# HDMI_Connector_for_RK3399.net
KiCad netlist of a schematic drawn in Altium Designer
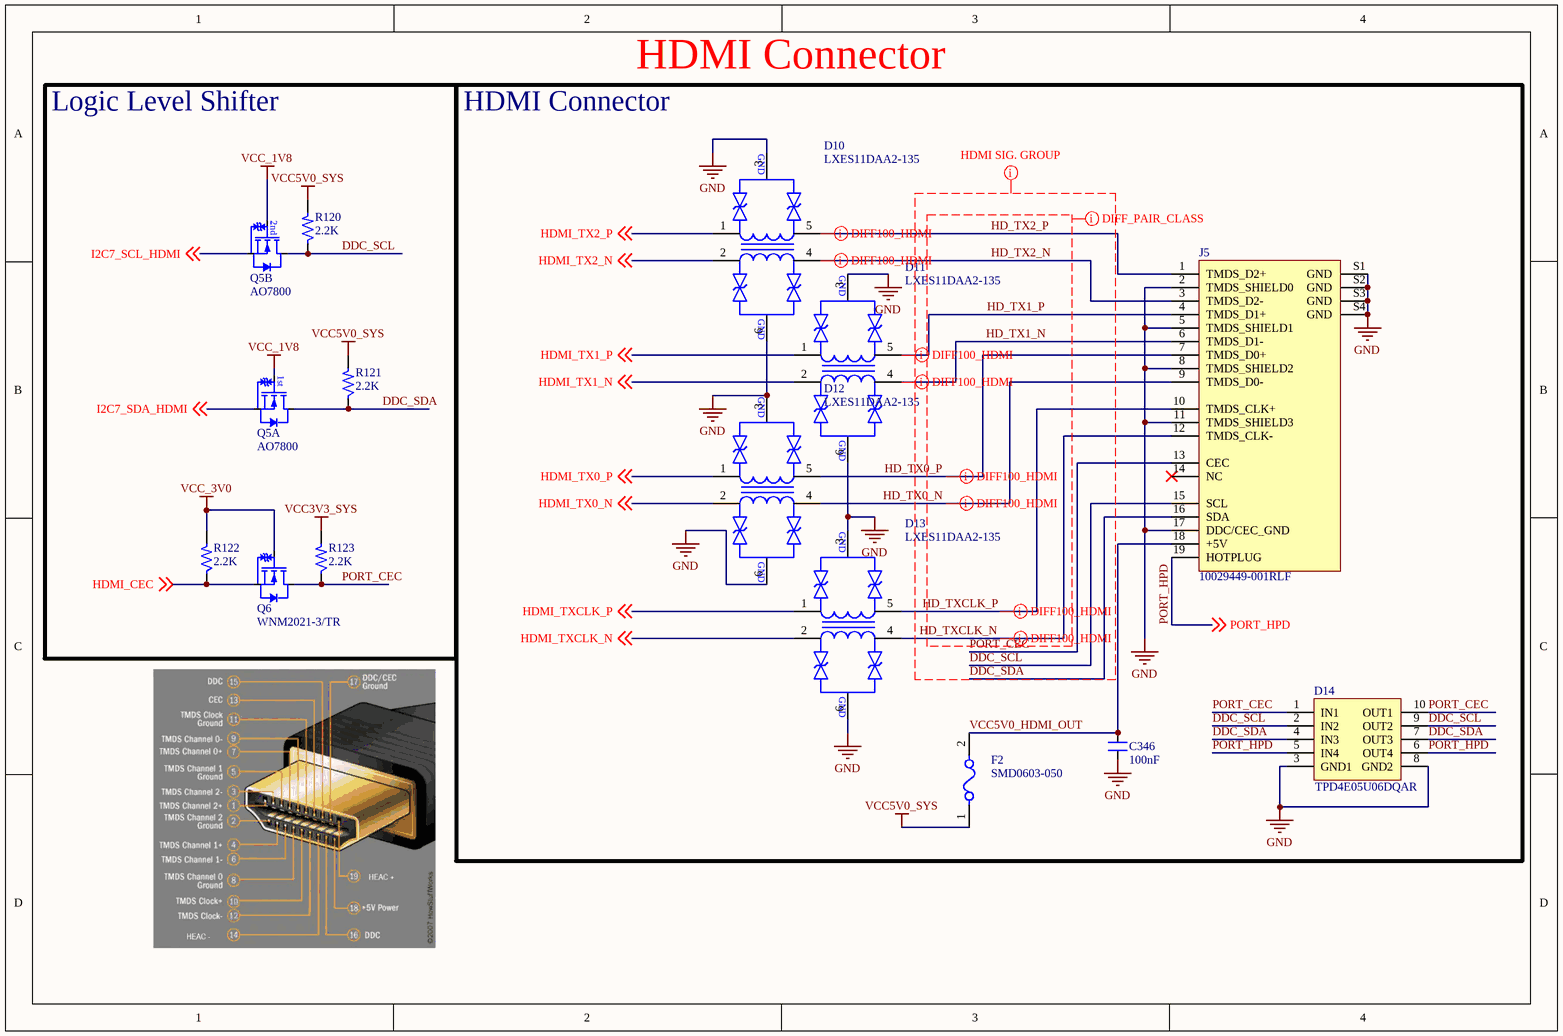
[diagram p0: HDMI Connector for RK3399.SchDoc]

(export (version "E")
  (design (tool "Eeschema 10.0.6"))
  (components
    (comp (ref "C346")
      (value "100nF")
      (footprint "CAP_0603")
      (description "0.1µF ±10% 10V Ceramic Capacitor X7R 0603 (1608 Metric)")
      (fields
        (field (name "MANUFACTURER") "Yageo")
        (field (name "MANUFACTURER PART NUMBER") "CC0603KRX7R6BB104")
      )
      (libsource (lib "RK3399 _Module_Schlib") (part "CAP_100nF-10V-5%-0603"))
    )
    (comp (ref "D10")
      (value "LXES11DAA2-135")
      (footprint "DIO_LXES11D_SMD")
      (description "Clamp Ipp Tvs Diode Surface Mount 10-SMD")
      (fields (field (name "MANUFACTURER") "Murata Electronics"))
      (libsource (lib "RK3399 _Module_Schlib") (part "DIO-T-A_5V-6SMD"))
    )
    (comp (ref "D11")
      (value "LXES11DAA2-135")
      (footprint "DIO_LXES11D_SMD")
      (description "Clamp Ipp Tvs Diode Surface Mount 10-SMD")
      (fields (field (name "MANUFACTURER") "Murata Electronics"))
      (libsource (lib "RK3399 _Module_Schlib") (part "DIO-T-A_5V-6SMD"))
    )
    (comp (ref "D12")
      (value "LXES11DAA2-135")
      (footprint "DIO_LXES11D_SMD")
      (description "Clamp Ipp Tvs Diode Surface Mount 10-SMD")
      (fields (field (name "MANUFACTURER") "Murata Electronics"))
      (libsource (lib "RK3399 _Module_Schlib") (part "DIO-T-A_5V-6SMD"))
    )
    (comp (ref "D13")
      (value "LXES11DAA2-135")
      (footprint "DIO_LXES11D_SMD")
      (description "Clamp Ipp Tvs Diode Surface Mount 10-SMD")
      (fields (field (name "MANUFACTURER") "Murata Electronics"))
      (libsource (lib "RK3399 _Module_Schlib") (part "DIO-T-A_5V-6SMD"))
    )
    (comp (ref "D14")
      (value "TPD4E05U06DQAR")
      (footprint "DIO_USON-10_SMD")
      (description "14V Clamp 2.5A (8/20µs) Ipp Tvs Diode Surface Mount 10-USON (2.5x1)")
      (fields (field (name "MANUFACTURER") "Texas Instruments"))
      (libsource (lib "RK3399 _Module_Schlib") (part "DIO-T_5.5V-14V-2.5A-10-USON"))
    )
    (comp (ref "F2")
      (value "SMD0603-050")
      (footprint "RES_0603")
      (description "6V 1A 0603 PTC Resettable Fuses RoHS")
      (fields (field (name "MANUFACTURER") "TECHFUSE"))
      (libsource (lib "RK3399 _Module_Schlib") (part "FUSE_1A-6V-0603"))
    )
    (comp (ref "J5")
      (value "10029449-001RLF")
      (footprint "CON19_19.6_10029449-001RLF_TH_RA")
      (description "HDMI HDMI 1.4 Receptacle Connector 19 Position Surface Mount, Right Angle; Through Hole")
      (fields (field (name "MANUFACTURER") "Amphenol ICC (FCI)"))
      (libsource (lib "EsteemPCB_COB_Course_intlib") (part "CON-HDMI_10029449-001RLF-RA-TH"))
    )
    (comp (ref "Q5")
      (value "AO7800")
      (footprint "SOT363-6")
      (description "DualNChannel 20V 900mA 900mV @ 250uA 300mΩ @ 900mA,4.5V 300mW SC-70-6(SOT-363) MOSFET RoHS")
      (fields (field (name "MANUFACTURER") "Alpha & Omega Semicon"))
      (libsource (lib "RK3399 _Module_Schlib") (part "MOSFET-N_20V-0.9A-SOT-363"))
    )
    (comp (ref "Q6")
      (value "WNM2021-3/TR")
      (footprint "SOT-323-3")
      (description "N Channel 20V 820mA 850mV @ 250uA 310mΩ @ 550mA,4.5V 310mW SOT-323(SC-70) MOSFET RoHS")
      (fields (field (name "MANUFACTURER") "WILLSEMI(Will Semicon)"))
      (libsource (lib "RK3399 _Module_Schlib") (part "MOSFET-N_20V-820mA-SOT-323"))
    )
    (comp (ref "R120")
      (value "2.2K")
      (footprint "RES_0603")
      (description "2.2 kOhms ±1% 0.1W, 1/10W Chip Resistor 0603 (1608 Metric) Thick Film")
      (fields
        (field (name "MANUFACTURER") "Yageo")
        (field (name "MANUFACTURER PART NUMBER") "RC0603FR-072K2L")
      )
      (libsource (lib "RK3399 _Module_Schlib") (part "RES_2.2K-0.1W-1%-0603"))
    )
    (comp (ref "R121")
      (value "2.2K")
      (footprint "RES_0603")
      (description "2.2 kOhms ±1% 0.1W, 1/10W Chip Resistor 0603 (1608 Metric) Thick Film")
      (fields
        (field (name "MANUFACTURER") "Yageo")
        (field (name "MANUFACTURER PART NUMBER") "RC0603FR-072K2L")
      )
      (libsource (lib "RK3399 _Module_Schlib") (part "RES_2.2K-0.1W-1%-0603"))
    )
    (comp (ref "R122")
      (value "2.2K")
      (footprint "RES_0603")
      (description "2.2 kOhms ±1% 0.1W, 1/10W Chip Resistor 0603 (1608 Metric) Thick Film")
      (fields
        (field (name "MANUFACTURER") "Yageo")
        (field (name "MANUFACTURER PART NUMBER") "RC0603FR-072K2L")
      )
      (libsource (lib "RK3399 _Module_Schlib") (part "RES_2.2K-0.1W-1%-0603"))
    )
    (comp (ref "R123")
      (value "2.2K")
      (footprint "RES_0603")
      (description "2.2 kOhms ±1% 0.1W, 1/10W Chip Resistor 0603 (1608 Metric) Thick Film")
      (fields
        (field (name "MANUFACTURER") "Yageo")
        (field (name "MANUFACTURER PART NUMBER") "RC0603FR-072K2L")
      )
      (libsource (lib "RK3399 _Module_Schlib") (part "RES_2.2K-0.1W-1%-0603"))
    )
  )
  (nets
    (net (code "1") (name "/DDC_SCL") (class "Default")
      (node (ref "D14") (pin "2") (pinfunction "IN2_2") (pintype "passive"))
      (node (ref "D14") (pin "9") (pinfunction "OUT2_9") (pintype "passive"))
      (node (ref "J5") (pin "15") (pinfunction "SCL_15") (pintype "passive"))
      (node (ref "Q5") (pin "3") (pinfunction "D2_3") (pintype "passive"))
      (node (ref "R120") (pin "1") (pinfunction "1_1") (pintype "passive"))
    )
    (net (code "2") (name "/DDC_SDA") (class "Default")
      (node (ref "D14") (pin "4") (pinfunction "IN3_4") (pintype "passive"))
      (node (ref "D14") (pin "7") (pinfunction "OUT3_7") (pintype "passive"))
      (node (ref "J5") (pin "16") (pinfunction "SDA_16") (pintype "passive"))
      (node (ref "Q5") (pin "6") (pinfunction "D1_6") (pintype "passive"))
      (node (ref "R121") (pin "1") (pinfunction "1_1") (pintype "passive"))
    )
    (net (code "3") (name "/HD_TX0_N") (class "Default")
      (node (ref "D12") (pin "4") (pinfunction "4_4") (pintype "passive"))
      (node (ref "J5") (pin "9") (pinfunction "TMDS_D0-_9") (pintype "passive"))
    )
    (net (code "4") (name "/HD_TX0_P") (class "Default")
      (node (ref "D12") (pin "5") (pinfunction "5_5") (pintype "passive"))
      (node (ref "J5") (pin "7") (pinfunction "TMDS_D0+_7") (pintype "passive"))
    )
    (net (code "5") (name "/HD_TX1_N") (class "Default")
      (node (ref "D11") (pin "4") (pinfunction "4_4") (pintype "passive"))
      (node (ref "J5") (pin "6") (pinfunction "TMDS_D1-_6") (pintype "passive"))
    )
    (net (code "6") (name "/HD_TX1_P") (class "Default")
      (node (ref "D11") (pin "5") (pinfunction "5_5") (pintype "passive"))
      (node (ref "J5") (pin "4") (pinfunction "TMDS_D1+_4") (pintype "passive"))
    )
    (net (code "7") (name "/HD_TX2_N") (class "Default")
      (node (ref "D10") (pin "4") (pinfunction "4_4") (pintype "passive"))
      (node (ref "J5") (pin "3") (pinfunction "TMDS_D2-_3") (pintype "passive"))
    )
    (net (code "8") (name "/HD_TX2_P") (class "Default")
      (node (ref "D10") (pin "5") (pinfunction "5_5") (pintype "passive"))
      (node (ref "J5") (pin "1") (pinfunction "TMDS_D2+_1") (pintype "passive"))
    )
    (net (code "9") (name "/HD_TXCLK_N") (class "Default")
      (node (ref "D13") (pin "4") (pinfunction "4_4") (pintype "passive"))
      (node (ref "J5") (pin "12") (pinfunction "TMDS_CLK-_12") (pintype "passive"))
    )
    (net (code "10") (name "/HD_TXCLK_P") (class "Default")
      (node (ref "D13") (pin "5") (pinfunction "5_5") (pintype "passive"))
      (node (ref "J5") (pin "10") (pinfunction "TMDS_CLK+_10") (pintype "passive"))
    )
    (net (code "11") (name "/PORT_CEC") (class "Default")
      (node (ref "D14") (pin "1") (pinfunction "IN1_1") (pintype "passive"))
      (node (ref "D14") (pin "10") (pinfunction "OUT1_10") (pintype "passive"))
      (node (ref "J5") (pin "13") (pinfunction "CEC_13") (pintype "passive"))
      (node (ref "Q6") (pin "3") (pinfunction "D_3") (pintype "passive"))
      (node (ref "R123") (pin "1") (pinfunction "1_1") (pintype "passive"))
    )
    (net (code "12") (name "/VCC5V0_HDMI_OUT") (class "Default")
      (node (ref "C346") (pin "2") (pinfunction "2_2") (pintype "passive"))
      (node (ref "F2") (pin "2") (pinfunction "2_2") (pintype "passive"))
      (node (ref "J5") (pin "18") (pinfunction "+5V_18") (pintype "passive"))
    )
    (net (code "13") (name "GND") (class "Default")
      (node (ref "C346") (pin "1") (pinfunction "1_1") (pintype "passive"))
      (node (ref "D10") (pin "3") (pinfunction "5_3") (pintype "passive"))
      (node (ref "D10") (pin "6") (pinfunction "6_6") (pintype "passive"))
      (node (ref "D11") (pin "3") (pinfunction "5_3") (pintype "passive"))
      (node (ref "D11") (pin "6") (pinfunction "6_6") (pintype "passive"))
      (node (ref "D12") (pin "3") (pinfunction "5_3") (pintype "passive"))
      (node (ref "D12") (pin "6") (pinfunction "6_6") (pintype "passive"))
      (node (ref "D13") (pin "3") (pinfunction "5_3") (pintype "passive"))
      (node (ref "D13") (pin "6") (pinfunction "6_6") (pintype "passive"))
      (node (ref "D14") (pin "3") (pinfunction "GND1_3") (pintype "passive"))
      (node (ref "D14") (pin "8") (pinfunction "GND2_8") (pintype "passive"))
      (node (ref "J5") (pin "11") (pinfunction "TMDS_SHIELD3_11") (pintype "passive"))
      (node (ref "J5") (pin "17") (pinfunction "DDC/CEC_GND_17") (pintype "passive"))
      (node (ref "J5") (pin "2") (pinfunction "TMDS_SHIELD0_2") (pintype "passive"))
      (node (ref "J5") (pin "5") (pinfunction "TMDS_SHIELD1_5") (pintype "passive"))
      (node (ref "J5") (pin "8") (pinfunction "TMDS_SHIELD2_8") (pintype "passive"))
      (node (ref "J5") (pin "S1") (pinfunction "GND_S1") (pintype "passive"))
      (node (ref "J5") (pin "S2") (pinfunction "GND_S2") (pintype "passive"))
      (node (ref "J5") (pin "S3") (pinfunction "GND_S3") (pintype "passive"))
      (node (ref "J5") (pin "S4") (pinfunction "GND_S4") (pintype "passive"))
    )
    (net (code "14") (name "HDMI_CEC") (class "Default")
      (node (ref "Q6") (pin "2") (pinfunction "S_2") (pintype "passive"))
      (node (ref "R122") (pin "1") (pinfunction "1_1") (pintype "passive"))
    )
    (net (code "15") (name "HDMI_TX0_N") (class "Default")
      (node (ref "D12") (pin "2") (pinfunction "2_2") (pintype "passive"))
    )
    (net (code "16") (name "HDMI_TX0_P") (class "Default")
      (node (ref "D12") (pin "1") (pinfunction "1_1") (pintype "passive"))
    )
    (net (code "17") (name "HDMI_TX1_N") (class "Default")
      (node (ref "D11") (pin "2") (pinfunction "2_2") (pintype "passive"))
    )
    (net (code "18") (name "HDMI_TX1_P") (class "Default")
      (node (ref "D11") (pin "1") (pinfunction "1_1") (pintype "passive"))
    )
    (net (code "19") (name "HDMI_TX2_N") (class "Default")
      (node (ref "D10") (pin "2") (pinfunction "2_2") (pintype "passive"))
    )
    (net (code "20") (name "HDMI_TX2_P") (class "Default")
      (node (ref "D10") (pin "1") (pinfunction "1_1") (pintype "passive"))
    )
    (net (code "21") (name "HDMI_TXCLK_N") (class "Default")
      (node (ref "D13") (pin "2") (pinfunction "2_2") (pintype "passive"))
    )
    (net (code "22") (name "HDMI_TXCLK_P") (class "Default")
      (node (ref "D13") (pin "1") (pinfunction "1_1") (pintype "passive"))
    )
    (net (code "23") (name "I2C7_SCL_HDMI") (class "Default")
      (node (ref "Q5") (pin "4") (pinfunction "S2_4") (pintype "passive"))
    )
    (net (code "24") (name "I2C7_SDA_HDMI") (class "Default")
      (node (ref "Q5") (pin "1") (pinfunction "S1_1") (pintype "passive"))
    )
    (net (code "25") (name "PORT_HPD") (class "Default")
      (node (ref "D14") (pin "5") (pinfunction "IN4_5") (pintype "passive"))
      (node (ref "D14") (pin "6") (pinfunction "OUT4_6") (pintype "passive"))
      (node (ref "J5") (pin "19") (pinfunction "HOTPLUG_19") (pintype "passive"))
    )
    (net (code "26") (name "VCC3V3_SYS") (class "Default")
      (node (ref "R123") (pin "2") (pinfunction "2_2") (pintype "passive"))
    )
    (net (code "27") (name "VCC5V0_SYS") (class "Default")
      (node (ref "F2") (pin "1") (pinfunction "1_1") (pintype "passive"))
      (node (ref "R120") (pin "2") (pinfunction "2_2") (pintype "passive"))
      (node (ref "R121") (pin "2") (pinfunction "2_2") (pintype "passive"))
    )
    (net (code "28") (name "VCC_1V8") (class "Default")
      (node (ref "Q5") (pin "2") (pinfunction "G1_2") (pintype "passive"))
      (node (ref "Q5") (pin "5") (pinfunction "G2_5") (pintype "passive"))
    )
    (net (code "29") (name "VCC_3V0") (class "Default")
      (node (ref "Q6") (pin "1") (pinfunction "G_1") (pintype "passive"))
      (node (ref "R122") (pin "2") (pinfunction "2_2") (pintype "passive"))
    )
    (net (code "30") (name "unconnected-(J5-NC-Pad14)") (class "Default")
      (node (ref "J5") (pin "14") (pinfunction "NC_14") (pintype "passive+no_connect"))
    )
  )
)
